# Power.net
KiCad netlist of a schematic drawn in Altium Designer
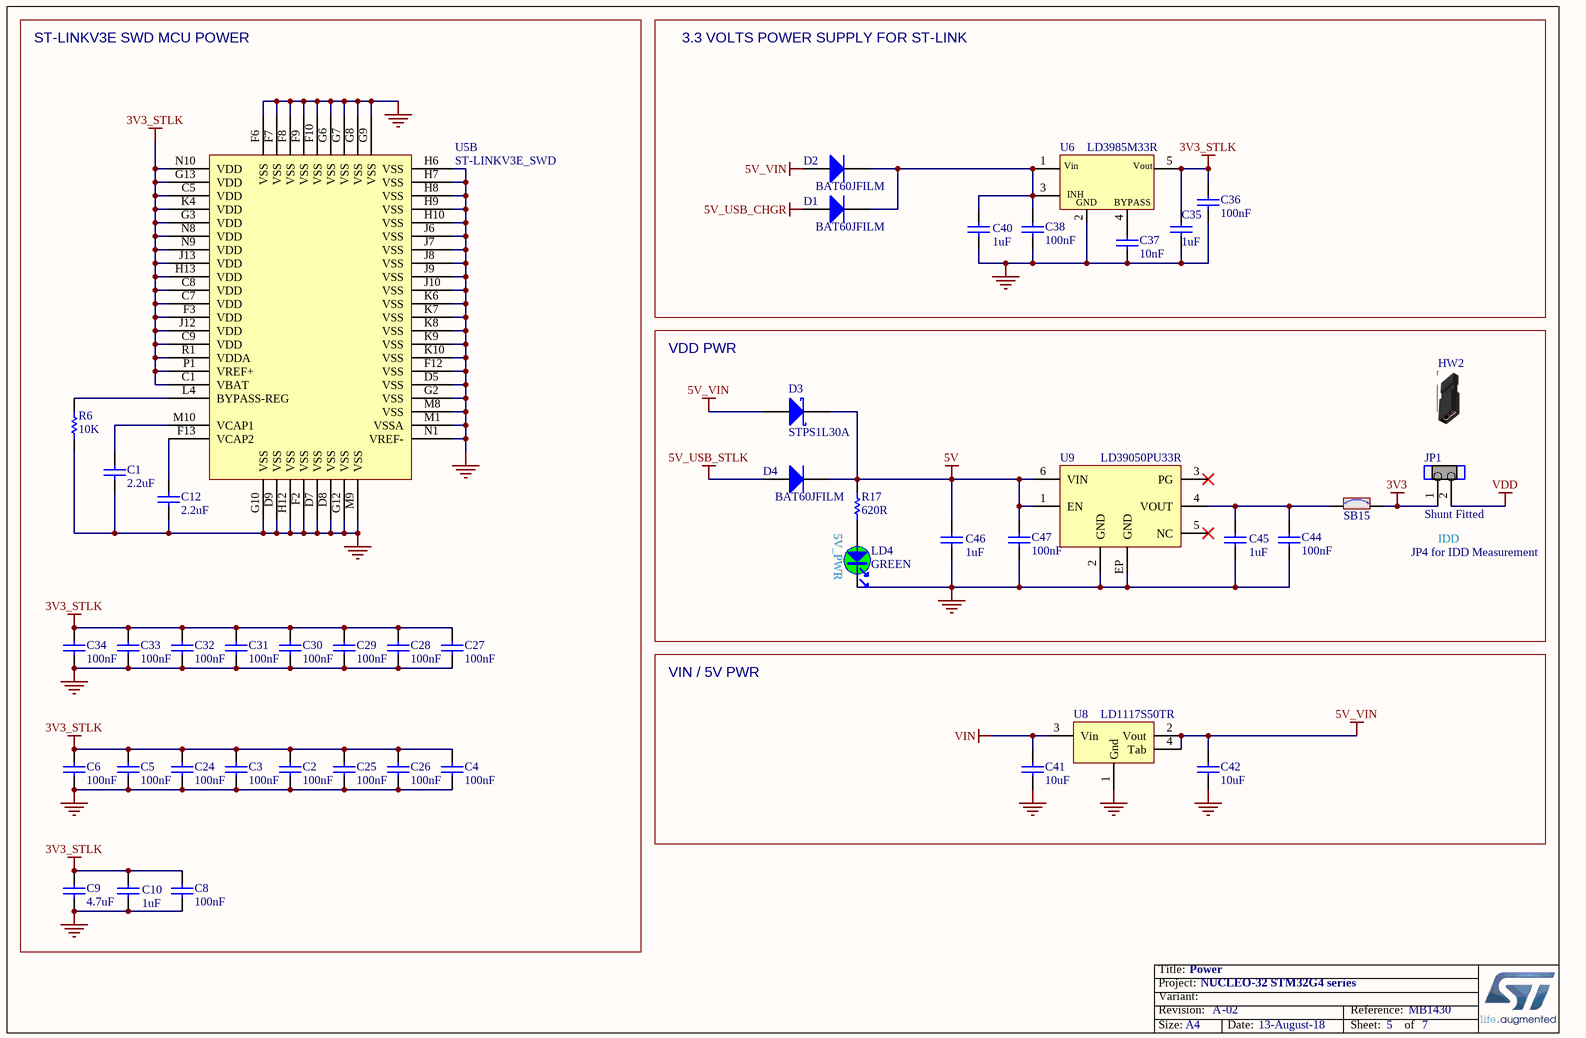
[diagram p0: Power.SchDoc]

(export (version "E")
  (design (tool "Eeschema 10.0.6"))
  (components
    (comp (ref "C1")
      (value "2.2uF")
      (footprint "C0603")
      (description "Capacitor, MLCC, 2.2uF, 10V, X5R, 10%, 0603, T=0,8mm")
      (fields
        (field (name "INTERNAL_PART_NUMBER") "MCD-00012")
        (field (name "MANUFACTURER_PART_NUMBER") "CC0603KRX5R6BB225")
        (field (name "PROVIDED_BY") "SUBCO")
      )
      (libsource (lib "MCD_PARTS_database") (part "Capacitor"))
    )
    (comp (ref "C2")
      (value "100nF")
      (footprint "C0402")
      (description "Capacitor, MLCC, 100nF, 16V, X7R, 10%, 0402, T=0,5mm")
      (fields
        (field (name "INTERNAL_PART_NUMBER") "MCD-00102")
        (field (name "MANUFACTURER_PART_NUMBER") "CC0402KRX7R7BB104")
        (field (name "PROVIDED_BY") "SUBCO")
      )
      (libsource (lib "MCD_PARTS_database") (part "Capacitor"))
    )
    (comp (ref "C3")
      (value "100nF")
      (footprint "C0402")
      (description "Capacitor, MLCC, 100nF, 16V, X7R, 10%, 0402, T=0,5mm")
      (fields
        (field (name "INTERNAL_PART_NUMBER") "MCD-00102")
        (field (name "MANUFACTURER_PART_NUMBER") "CC0402KRX7R7BB104")
        (field (name "PROVIDED_BY") "SUBCO")
      )
      (libsource (lib "MCD_PARTS_database") (part "Capacitor"))
    )
    (comp (ref "C4")
      (value "100nF")
      (footprint "C0402")
      (description "Capacitor, MLCC, 100nF, 16V, X7R, 10%, 0402, T=0,5mm")
      (fields
        (field (name "INTERNAL_PART_NUMBER") "MCD-00102")
        (field (name "MANUFACTURER_PART_NUMBER") "CC0402KRX7R7BB104")
        (field (name "PROVIDED_BY") "SUBCO")
      )
      (libsource (lib "MCD_PARTS_database") (part "Capacitor"))
    )
    (comp (ref "C5")
      (value "100nF")
      (footprint "C0402")
      (description "Capacitor, MLCC, 100nF, 16V, X7R, 10%, 0402, T=0,5mm")
      (fields
        (field (name "INTERNAL_PART_NUMBER") "MCD-00102")
        (field (name "MANUFACTURER_PART_NUMBER") "CC0402KRX7R7BB104")
        (field (name "PROVIDED_BY") "SUBCO")
      )
      (libsource (lib "MCD_PARTS_database") (part "Capacitor"))
    )
    (comp (ref "C6")
      (value "100nF")
      (footprint "C0402")
      (description "Capacitor, MLCC, 100nF, 16V, X7R, 10%, 0402, T=0,5mm")
      (fields
        (field (name "INTERNAL_PART_NUMBER") "MCD-00102")
        (field (name "MANUFACTURER_PART_NUMBER") "CC0402KRX7R7BB104")
        (field (name "PROVIDED_BY") "SUBCO")
      )
      (libsource (lib "MCD_PARTS_database") (part "Capacitor"))
    )
    (comp (ref "C8")
      (value "100nF")
      (footprint "C0402")
      (description "Capacitor, MLCC, 100nF, 16V, X7R, 10%, 0402, T=0,5mm")
      (fields
        (field (name "INTERNAL_PART_NUMBER") "MCD-00102")
        (field (name "MANUFACTURER_PART_NUMBER") "CC0402KRX7R7BB104")
        (field (name "PROVIDED_BY") "SUBCO")
      )
      (libsource (lib "MCD_PARTS_database") (part "Capacitor"))
    )
    (comp (ref "C9")
      (value "4.7uF")
      (footprint "C0603")
      (description "Capacitor, MLCC, 4.7uF, 16V, X5R, 10%, 0603, T=0.8mm")
      (fields
        (field (name "INTERNAL_PART_NUMBER") "MCD-00009")
        (field (name "MANUFACTURER_PART_NUMBER") "CC0603KRX5R7BB475")
        (field (name "PROVIDED_BY") "SUBCO")
      )
      (libsource (lib "MCD_PARTS_database") (part "Capacitor"))
    )
    (comp (ref "C10")
      (value "1uF")
      (footprint "C0603")
      (description "Capacitor, MLCC, 1uF, 16V, X5R, 10%, 0603, T=0,8mm")
      (fields
        (field (name "INTERNAL_PART_NUMBER") "MCD-00010")
        (field (name "MANUFACTURER_PART_NUMBER") "CC0603KRX5R7BB105")
        (field (name "PROVIDED_BY") "SUBCO")
      )
      (libsource (lib "MCD_PARTS_database") (part "Capacitor"))
    )
    (comp (ref "C12")
      (value "2.2uF")
      (footprint "C0603")
      (description "Capacitor, MLCC, 2.2uF, 10V, X5R, 10%, 0603, T=0,8mm")
      (fields
        (field (name "INTERNAL_PART_NUMBER") "MCD-00012")
        (field (name "MANUFACTURER_PART_NUMBER") "CC0603KRX5R6BB225")
        (field (name "PROVIDED_BY") "SUBCO")
      )
      (libsource (lib "MCD_PARTS_database") (part "Capacitor"))
    )
    (comp (ref "C24")
      (value "100nF")
      (footprint "C0402")
      (description "Capacitor, MLCC, 100nF, 16V, X7R, 10%, 0402, T=0,5mm")
      (fields
        (field (name "INTERNAL_PART_NUMBER") "MCD-00102")
        (field (name "MANUFACTURER_PART_NUMBER") "CC0402KRX7R7BB104")
        (field (name "PROVIDED_BY") "SUBCO")
      )
      (libsource (lib "MCD_PARTS_database") (part "Capacitor"))
    )
    (comp (ref "C25")
      (value "100nF")
      (footprint "C0402")
      (description "Capacitor, MLCC, 100nF, 16V, X7R, 10%, 0402, T=0,5mm")
      (fields
        (field (name "INTERNAL_PART_NUMBER") "MCD-00102")
        (field (name "MANUFACTURER_PART_NUMBER") "CC0402KRX7R7BB104")
        (field (name "PROVIDED_BY") "SUBCO")
      )
      (libsource (lib "MCD_PARTS_database") (part "Capacitor"))
    )
    (comp (ref "C26")
      (value "100nF")
      (footprint "C0402")
      (description "Capacitor, MLCC, 100nF, 16V, X7R, 10%, 0402, T=0,5mm")
      (fields
        (field (name "INTERNAL_PART_NUMBER") "MCD-00102")
        (field (name "MANUFACTURER_PART_NUMBER") "CC0402KRX7R7BB104")
        (field (name "PROVIDED_BY") "SUBCO")
      )
      (libsource (lib "MCD_PARTS_database") (part "Capacitor"))
    )
    (comp (ref "C27")
      (value "100nF")
      (footprint "C0402")
      (description "Capacitor, MLCC, 100nF, 16V, X7R, 10%, 0402, T=0,5mm")
      (fields
        (field (name "INTERNAL_PART_NUMBER") "MCD-00102")
        (field (name "MANUFACTURER_PART_NUMBER") "CC0402KRX7R7BB104")
        (field (name "PROVIDED_BY") "SUBCO")
      )
      (libsource (lib "MCD_PARTS_database") (part "Capacitor"))
    )
    (comp (ref "C28")
      (value "100nF")
      (footprint "C0402")
      (description "Capacitor, MLCC, 100nF, 16V, X7R, 10%, 0402, T=0,5mm")
      (fields
        (field (name "INTERNAL_PART_NUMBER") "MCD-00102")
        (field (name "MANUFACTURER_PART_NUMBER") "CC0402KRX7R7BB104")
        (field (name "PROVIDED_BY") "SUBCO")
      )
      (libsource (lib "MCD_PARTS_database") (part "Capacitor"))
    )
    (comp (ref "C29")
      (value "100nF")
      (footprint "C0402")
      (description "Capacitor, MLCC, 100nF, 16V, X7R, 10%, 0402, T=0,5mm")
      (fields
        (field (name "INTERNAL_PART_NUMBER") "MCD-00102")
        (field (name "MANUFACTURER_PART_NUMBER") "CC0402KRX7R7BB104")
        (field (name "PROVIDED_BY") "SUBCO")
      )
      (libsource (lib "MCD_PARTS_database") (part "Capacitor"))
    )
    (comp (ref "C30")
      (value "100nF")
      (footprint "C0402")
      (description "Capacitor, MLCC, 100nF, 16V, X7R, 10%, 0402, T=0,5mm")
      (fields
        (field (name "INTERNAL_PART_NUMBER") "MCD-00102")
        (field (name "MANUFACTURER_PART_NUMBER") "CC0402KRX7R7BB104")
        (field (name "PROVIDED_BY") "SUBCO")
      )
      (libsource (lib "MCD_PARTS_database") (part "Capacitor"))
    )
    (comp (ref "C31")
      (value "100nF")
      (footprint "C0402")
      (description "Capacitor, MLCC, 100nF, 16V, X7R, 10%, 0402, T=0,5mm")
      (fields
        (field (name "INTERNAL_PART_NUMBER") "MCD-00102")
        (field (name "MANUFACTURER_PART_NUMBER") "CC0402KRX7R7BB104")
        (field (name "PROVIDED_BY") "SUBCO")
      )
      (libsource (lib "MCD_PARTS_database") (part "Capacitor"))
    )
    (comp (ref "C32")
      (value "100nF")
      (footprint "C0402")
      (description "Capacitor, MLCC, 100nF, 16V, X7R, 10%, 0402, T=0,5mm")
      (fields
        (field (name "INTERNAL_PART_NUMBER") "MCD-00102")
        (field (name "MANUFACTURER_PART_NUMBER") "CC0402KRX7R7BB104")
        (field (name "PROVIDED_BY") "SUBCO")
      )
      (libsource (lib "MCD_PARTS_database") (part "Capacitor"))
    )
    (comp (ref "C33")
      (value "100nF")
      (footprint "C0402")
      (description "Capacitor, MLCC, 100nF, 16V, X7R, 10%, 0402, T=0,5mm")
      (fields
        (field (name "INTERNAL_PART_NUMBER") "MCD-00102")
        (field (name "MANUFACTURER_PART_NUMBER") "CC0402KRX7R7BB104")
        (field (name "PROVIDED_BY") "SUBCO")
      )
      (libsource (lib "MCD_PARTS_database") (part "Capacitor"))
    )
    (comp (ref "C34")
      (value "100nF")
      (footprint "C0402")
      (description "Capacitor, MLCC, 100nF, 16V, X7R, 10%, 0402, T=0,5mm")
      (fields
        (field (name "INTERNAL_PART_NUMBER") "MCD-00102")
        (field (name "MANUFACTURER_PART_NUMBER") "CC0402KRX7R7BB104")
        (field (name "PROVIDED_BY") "SUBCO")
      )
      (libsource (lib "MCD_PARTS_database") (part "Capacitor"))
    )
    (comp (ref "C35")
      (value "1uF")
      (footprint "C0603")
      (description "Capacitor, MLCC, 1uF, 16V, X5R, 10%, 0603, T=0,8mm")
      (fields
        (field (name "INTERNAL_PART_NUMBER") "MCD-00010")
        (field (name "MANUFACTURER_PART_NUMBER") "CC0603KRX5R7BB105")
        (field (name "PROVIDED_BY") "SUBCO")
      )
      (libsource (lib "MCD_PARTS_database") (part "Capacitor"))
    )
    (comp (ref "C36")
      (value "100nF")
      (footprint "C0402")
      (description "Capacitor, MLCC, 100nF, 16V, X7R, 10%, 0402, T=0,5mm")
      (fields
        (field (name "INTERNAL_PART_NUMBER") "MCD-00102")
        (field (name "MANUFACTURER_PART_NUMBER") "CC0402KRX7R7BB104")
        (field (name "PROVIDED_BY") "SUBCO")
      )
      (libsource (lib "MCD_PARTS_database") (part "Capacitor"))
    )
    (comp (ref "C37")
      (value "10nF")
      (footprint "C0402")
      (description "Capacitor, MLCC, 10nF, 16V, X7R, 10%, 0402, T=0.5mm")
      (fields
        (field (name "INTERNAL_PART_NUMBER") "MCD-00011")
        (field (name "MANUFACTURER_PART_NUMBER") "CC0402KRX7R7BB103")
        (field (name "PROVIDED_BY") "SUBCO")
      )
      (libsource (lib "MCD_PARTS_database") (part "Capacitor"))
    )
    (comp (ref "C38")
      (value "100nF")
      (footprint "C0402")
      (description "Capacitor, MLCC, 100nF, 16V, X7R, 10%, 0402, T=0,5mm")
      (fields
        (field (name "INTERNAL_PART_NUMBER") "MCD-00102")
        (field (name "MANUFACTURER_PART_NUMBER") "CC0402KRX7R7BB104")
        (field (name "PROVIDED_BY") "SUBCO")
      )
      (libsource (lib "MCD_PARTS_database") (part "Capacitor"))
    )
    (comp (ref "C40")
      (value "1uF")
      (footprint "C0603")
      (description "Capacitor, MLCC, 1uF, 16V, X5R, 10%, 0603, T=0,8mm")
      (fields
        (field (name "INTERNAL_PART_NUMBER") "MCD-00010")
        (field (name "MANUFACTURER_PART_NUMBER") "CC0603KRX5R7BB105")
        (field (name "PROVIDED_BY") "SUBCO")
      )
      (libsource (lib "MCD_PARTS_database") (part "Capacitor"))
    )
    (comp (ref "C41")
      (value "10uF")
      (footprint "C0805")
      (description "Capacitor, MLCC, 10uF, 25V, X5R, 10%, 0805, T=0,85mm")
      (fields
        (field (name "INTERNAL_PART_NUMBER") "MCD-00014")
        (field (name "MANUFACTURER_PART_NUMBER") "CC0805KRX5R8BB106")
        (field (name "PROVIDED_BY") "SUBCO")
      )
      (libsource (lib "MCD_PARTS_database") (part "Capacitor"))
    )
    (comp (ref "C42")
      (value "10uF")
      (footprint "C0805")
      (description "Capacitor, MLCC, 10uF, 25V, X5R, 10%, 0805, T=0,85mm")
      (fields
        (field (name "INTERNAL_PART_NUMBER") "MCD-00014")
        (field (name "MANUFACTURER_PART_NUMBER") "CC0805KRX5R8BB106")
        (field (name "PROVIDED_BY") "SUBCO")
      )
      (libsource (lib "MCD_PARTS_database") (part "Capacitor"))
    )
    (comp (ref "C44")
      (value "100nF")
      (footprint "C0402")
      (description "Capacitor, MLCC, 100nF, 16V, X7R, 10%, 0402, T=0,5mm")
      (fields
        (field (name "INTERNAL_PART_NUMBER") "MCD-00102")
        (field (name "MANUFACTURER_PART_NUMBER") "CC0402KRX7R7BB104")
        (field (name "PROVIDED_BY") "SUBCO")
      )
      (libsource (lib "MCD_PARTS_database") (part "Capacitor"))
    )
    (comp (ref "C45")
      (value "1uF")
      (footprint "C0603")
      (description "Capacitor, MLCC, 1uF, 16V, X5R, 10%, 0603, T=0,8mm")
      (fields
        (field (name "INTERNAL_PART_NUMBER") "MCD-00010")
        (field (name "MANUFACTURER_PART_NUMBER") "CC0603KRX5R7BB105")
        (field (name "PROVIDED_BY") "SUBCO")
      )
      (libsource (lib "MCD_PARTS_database") (part "Capacitor"))
    )
    (comp (ref "C46")
      (value "1uF")
      (footprint "C0603")
      (description "Capacitor, MLCC, 1uF, 16V, X5R, 10%, 0603, T=0,8mm")
      (fields
        (field (name "INTERNAL_PART_NUMBER") "MCD-00010")
        (field (name "MANUFACTURER_PART_NUMBER") "CC0603KRX5R7BB105")
        (field (name "PROVIDED_BY") "SUBCO")
      )
      (libsource (lib "MCD_PARTS_database") (part "Capacitor"))
    )
    (comp (ref "C47")
      (value "100nF")
      (footprint "C0402")
      (description "Capacitor, MLCC, 100nF, 16V, X7R, 10%, 0402, T=0,5mm")
      (fields
        (field (name "INTERNAL_PART_NUMBER") "MCD-00102")
        (field (name "MANUFACTURER_PART_NUMBER") "CC0402KRX7R7BB104")
        (field (name "PROVIDED_BY") "SUBCO")
      )
      (libsource (lib "MCD_PARTS_database") (part "Capacitor"))
    )
    (comp (ref "D1")
      (value "BAT60JFILM")
      (footprint "DIO_SOD323")
      (fields
        (field (name "INTERNAL_PART_NUMBER") "MCD-00034")
        (field (name "MANUFACTURER") "STMICROELECTRONICS")
        (field (name "BMS_PART_NUMBER") "9151097")
        (field (name "PROVIDED_BY") "SUBCO with ST control")
      )
      (libsource (lib "MCD_PARTS_database") (part "BAT60JFILM"))
    )
    (comp (ref "D2")
      (value "BAT60JFILM")
      (footprint "DIO_SOD323")
      (fields
        (field (name "INTERNAL_PART_NUMBER") "MCD-00034")
        (field (name "MANUFACTURER") "STMICROELECTRONICS")
        (field (name "BMS_PART_NUMBER") "9151097")
        (field (name "PROVIDED_BY") "SUBCO with ST control")
      )
      (libsource (lib "MCD_PARTS_database") (part "BAT60JFILM"))
    )
    (comp (ref "D3")
      (value "STPS1L30A")
      (footprint "DIO_SMA_1A_2K")
      (description "LOW DROP POWER SCHOTTKY RECTIFIER 1A 30V VF=0.3V")
      (fields
        (field (name "INTERNAL_PART_NUMBER") "MCD-01059")
        (field (name "MANUFACTURER") "STMICROELECTRONICS")
        (field (name "PROVIDED_BY") "SUBCO with ST control")
      )
      (libsource (lib "MCD_PARTS_database") (part "STPS1L40M"))
    )
    (comp (ref "D4")
      (value "BAT60JFILM")
      (footprint "DIO_SOD323")
      (fields
        (field (name "INTERNAL_PART_NUMBER") "MCD-00034")
        (field (name "MANUFACTURER") "STMICROELECTRONICS")
        (field (name "BMS_PART_NUMBER") "9151097")
        (field (name "PROVIDED_BY") "SUBCO with ST control")
      )
      (libsource (lib "MCD_PARTS_database") (part "BAT60JFILM"))
    )
    (comp (ref "HW2")
      (value "~")
      (description "SHUNT 1.27mm BLACK")
      (fields
        (field (name "INTERNAL_PART_NUMBER") "MCD-01409")
        (field (name "MANUFACTURER_PART_NUMBER") "266-101-10-00")
        (field (name "PROVIDED_BY") "SUBCO")
      )
      (libsource (lib "MCD_PARTS_database") (part "Shunt Black 1.27mm"))
    )
    (comp (ref "JP1")
      (value "Shunt Fitted")
      (footprint "CON_WP_707-2-02-2-20-00")
      (description "Header, 2x1, 1,27mm, Right Angled, Single Row, Height 3.05mm/1.27mm")
      (fields
        (field (name "INTERNAL_PART_NUMBER") "MCD-01428")
        (field (name "MANUFACTURER_PART_NUMBER") "707-2-02-2-20-00")
        (field (name "PROVIDED_BY") "SUBCO")
      )
      (libsource (lib "MCD_PARTS_database") (part "Jumper_Header1.27 2x1 Fitted"))
    )
    (comp (ref "LD4")
      (value "GREEN")
      (footprint "LED_0603_GREEN")
      (description "LED, Green, 0603")
      (fields
        (field (name "INTERNAL_PART_NUMBER") "MCD-00050")
        (field (name "MANUFACTURER_PART_NUMBER") "19-213SYGC/S530-E2/TR8")
        (field (name "PROVIDED_BY") "SUBCO")
      )
      (libsource (lib "MCD_PARTS_database") (part "LED_green"))
    )
    (comp (ref "R6")
      (value "10K")
      (footprint "R0402")
      (description "Resistor,10K,0402,1%,1/16W")
      (fields
        (field (name "INTERNAL_PART_NUMBER") "MCD-00053")
        (field (name "MANUFACTURER_PART_NUMBER") "RC0402FR-0710KL")
        (field (name "PROVIDED_BY") "SUBCO")
      )
      (libsource (lib "MCD_PARTS_database") (part "Resistor"))
    )
    (comp (ref "R17")
      (value "620R")
      (footprint "R0402")
      (description "Resistor,620R,0402,1%,1/16W")
      (fields
        (field (name "INTERNAL_PART_NUMBER") "MCD-00499")
        (field (name "MANUFACTURER_PART_NUMBER") "RC0402FR-07620RL")
        (field (name "PROVIDED_BY") "SUBCO")
      )
      (libsource (lib "MCD_PARTS_database") (part "Resistor"))
    )
    (comp (ref "SB15")
      (value "~")
      (footprint "SOLDER-BRIDGE_R0603-0R")
      (description "Solder Bridge ON")
      (fields
        (field (name "INTERNAL_PART_NUMBER") "MCD-00071")
        (field (name "MANUFACTURER_PART_NUMBER") "RC0603JR-070RL")
        (field (name "PROVIDED_BY") "SUBCO")
      )
      (libsource (lib "MCD_PARTS_database") (part "SB_ON"))
    )
    (comp (ref "U5")
      (value "ST-LINKV3E_SWD")
      (footprint "ICC_UFBGA201_176+25_10X10_P065")
      (description "STM32F723IEK  (STM32F7) BGA176")
      (fields
        (field (name "INTERNAL_PART_NUMBER") "MCD-00596")
        (field (name "MANUFACTURER_PART_NUMBER") "STM32F723IEK6")
        (field (name "PROVIDED_BY") "SUBCO with ST control")
      )
      (libsource (lib "MCD_PARTS_database") (part "ST-LINKV3E_SWD"))
    )
    (comp (ref "U6")
      (value "LD3985M33R")
      (footprint "REG_SOT23-5L")
      (description "Ultra low drop-low noise BiCMOS voltage, regulators low ESR capacitors compatible")
      (fields
        (field (name "INTERNAL_PART_NUMBER") "MCD-00086")
        (field (name "MANUFACTURER") "STMICROELECTRONICS")
        (field (name "PROVIDED_BY") "SUBCO with ST control")
      )
      (libsource (lib "MCD_PARTS_database") (part "LD3985M33R"))
    )
    (comp (ref "U8")
      (value "LD1117S50TR")
      (footprint "REG_SOT223-TAB")
      (description "IC REG LDO 5V 0.8A SOT223")
      (fields
        (field (name "INTERNAL_PART_NUMBER") "MCD-00088")
        (field (name "MANUFACTURER") "STMICROELECTRONICS")
        (field (name "PROVIDED_BY") "SUBCO with ST control")
      )
      (libsource (lib "MCD_PARTS_database") (part "LD1117S50TR"))
    )
    (comp (ref "U9")
      (value "LD39050PU33R")
      (footprint "ICC_DFN6-EPAD_3X3_P095")
      (description "Low quiescent current and low noise voltage regulators")
      (fields
        (field (name "INTERNAL_PART_NUMBER") "MCD-00215")
        (field (name "MANUFACTURER") "STMICROELECTRONICS")
        (field (name "PROVIDED_BY") "SUBCO with ST control")
      )
      (libsource (lib "MCD_PARTS_database") (part "LD39050PU33R"))
    )
  )
  (nets
    (net (code "1") (name "3V3") (class "Default")
      (node (ref "JP1") (pin "1") (pinfunction "1_1") (pintype "passive"))
      (node (ref "SB15") (pin "2") (pinfunction "2_2") (pintype "passive"))
    )
    (net (code "2") (name "3V3_STLK") (class "Default")
      (node (ref "C10") (pin "2") (pinfunction "2_2") (pintype "passive"))
      (node (ref "C2") (pin "2") (pinfunction "2_2") (pintype "passive"))
      (node (ref "C24") (pin "2") (pinfunction "2_2") (pintype "passive"))
      (node (ref "C25") (pin "2") (pinfunction "2_2") (pintype "passive"))
      (node (ref "C26") (pin "2") (pinfunction "2_2") (pintype "passive"))
      (node (ref "C27") (pin "2") (pinfunction "2_2") (pintype "passive"))
      (node (ref "C28") (pin "2") (pinfunction "2_2") (pintype "passive"))
      (node (ref "C29") (pin "2") (pinfunction "2_2") (pintype "passive"))
      (node (ref "C3") (pin "2") (pinfunction "2_2") (pintype "passive"))
      (node (ref "C30") (pin "2") (pinfunction "2_2") (pintype "passive"))
      (node (ref "C31") (pin "2") (pinfunction "2_2") (pintype "passive"))
      (node (ref "C32") (pin "2") (pinfunction "2_2") (pintype "passive"))
      (node (ref "C33") (pin "2") (pinfunction "2_2") (pintype "passive"))
      (node (ref "C34") (pin "2") (pinfunction "2_2") (pintype "passive"))
      (node (ref "C35") (pin "2") (pinfunction "2_2") (pintype "passive"))
      (node (ref "C36") (pin "2") (pinfunction "2_2") (pintype "passive"))
      (node (ref "C4") (pin "2") (pinfunction "2_2") (pintype "passive"))
      (node (ref "C5") (pin "2") (pinfunction "2_2") (pintype "passive"))
      (node (ref "C6") (pin "2") (pinfunction "2_2") (pintype "passive"))
      (node (ref "C8") (pin "2") (pinfunction "2_2") (pintype "passive"))
      (node (ref "C9") (pin "2") (pinfunction "2_2") (pintype "passive"))
      (node (ref "U5") (pin "C1") (pinfunction "VBAT_C1") (pintype "passive"))
      (node (ref "U5") (pin "C5") (pinfunction "VDD_C5") (pintype "passive"))
      (node (ref "U5") (pin "C7") (pinfunction "VDD_C7") (pintype "passive"))
      (node (ref "U5") (pin "C8") (pinfunction "VDD_C8") (pintype "passive"))
      (node (ref "U5") (pin "C9") (pinfunction "VDD_C9") (pintype "passive"))
      (node (ref "U5") (pin "F3") (pinfunction "VDD_F3") (pintype "passive"))
      (node (ref "U5") (pin "G13") (pinfunction "VDD_G13") (pintype "passive"))
      (node (ref "U5") (pin "G3") (pinfunction "VDD_G3") (pintype "passive"))
      (node (ref "U5") (pin "H13") (pinfunction "VDD_H13") (pintype "passive"))
      (node (ref "U5") (pin "J12") (pinfunction "VDD_J12") (pintype "passive"))
      (node (ref "U5") (pin "J13") (pinfunction "VDD_J13") (pintype "passive"))
      (node (ref "U5") (pin "K4") (pinfunction "VDD_K4") (pintype "passive"))
      (node (ref "U5") (pin "N10") (pinfunction "VDD_N10") (pintype "passive"))
      (node (ref "U5") (pin "N8") (pinfunction "VDD_N8") (pintype "passive"))
      (node (ref "U5") (pin "N9") (pinfunction "VDD_N9") (pintype "passive"))
      (node (ref "U5") (pin "P1") (pinfunction "VREF+_P1") (pintype "passive"))
      (node (ref "U5") (pin "R1") (pinfunction "VDDA_R1") (pintype "passive"))
      (node (ref "U6") (pin "5") (pinfunction "Vout_5") (pintype "passive"))
    )
    (net (code "3") (name "5V") (class "Default")
      (node (ref "C46") (pin "2") (pinfunction "2_2") (pintype "passive"))
      (node (ref "C47") (pin "2") (pinfunction "2_2") (pintype "passive"))
      (node (ref "D3") (pin "2") (pinfunction "K_2") (pintype "passive"))
      (node (ref "D4") (pin "2") (pinfunction "K_2") (pintype "passive"))
      (node (ref "R17") (pin "2") (pinfunction "2_2") (pintype "passive"))
      (node (ref "U9") (pin "1") (pinfunction "EN_1") (pintype "passive"))
      (node (ref "U9") (pin "6") (pinfunction "VIN_6") (pintype "passive"))
    )
    (net (code "4") (name "5V_USB_CHGR") (class "Default")
      (node (ref "D1") (pin "1") (pinfunction "A_1") (pintype "passive"))
    )
    (net (code "5") (name "5V_USB_STLK") (class "Default")
      (node (ref "D4") (pin "1") (pinfunction "A_1") (pintype "passive"))
    )
    (net (code "6") (name "5V_VIN") (class "Default")
      (node (ref "C42") (pin "2") (pinfunction "2_2") (pintype "passive"))
      (node (ref "D2") (pin "1") (pinfunction "A_1") (pintype "passive"))
      (node (ref "D3") (pin "1") (pinfunction "A_1") (pintype "passive"))
      (node (ref "U8") (pin "2") (pinfunction "Vout_2") (pintype "passive"))
      (node (ref "U8") (pin "4") (pinfunction "Tab_4") (pintype "passive"))
    )
    (net (code "7") (name "GND") (class "Default")
      (node (ref "C1") (pin "1") (pinfunction "1_1") (pintype "passive"))
      (node (ref "C10") (pin "1") (pinfunction "1_1") (pintype "passive"))
      (node (ref "C12") (pin "1") (pinfunction "1_1") (pintype "passive"))
      (node (ref "C2") (pin "1") (pinfunction "1_1") (pintype "passive"))
      (node (ref "C24") (pin "1") (pinfunction "1_1") (pintype "passive"))
      (node (ref "C25") (pin "1") (pinfunction "1_1") (pintype "passive"))
      (node (ref "C26") (pin "1") (pinfunction "1_1") (pintype "passive"))
      (node (ref "C27") (pin "1") (pinfunction "1_1") (pintype "passive"))
      (node (ref "C28") (pin "1") (pinfunction "1_1") (pintype "passive"))
      (node (ref "C29") (pin "1") (pinfunction "1_1") (pintype "passive"))
      (node (ref "C3") (pin "1") (pinfunction "1_1") (pintype "passive"))
      (node (ref "C30") (pin "1") (pinfunction "1_1") (pintype "passive"))
      (node (ref "C31") (pin "1") (pinfunction "1_1") (pintype "passive"))
      (node (ref "C32") (pin "1") (pinfunction "1_1") (pintype "passive"))
      (node (ref "C33") (pin "1") (pinfunction "1_1") (pintype "passive"))
      (node (ref "C34") (pin "1") (pinfunction "1_1") (pintype "passive"))
      (node (ref "C35") (pin "1") (pinfunction "1_1") (pintype "passive"))
      (node (ref "C36") (pin "1") (pinfunction "1_1") (pintype "passive"))
      (node (ref "C37") (pin "1") (pinfunction "1_1") (pintype "passive"))
      (node (ref "C38") (pin "1") (pinfunction "1_1") (pintype "passive"))
      (node (ref "C4") (pin "1") (pinfunction "1_1") (pintype "passive"))
      (node (ref "C40") (pin "1") (pinfunction "1_1") (pintype "passive"))
      (node (ref "C41") (pin "1") (pinfunction "1_1") (pintype "passive"))
      (node (ref "C42") (pin "1") (pinfunction "1_1") (pintype "passive"))
      (node (ref "C44") (pin "1") (pinfunction "1_1") (pintype "passive"))
      (node (ref "C45") (pin "1") (pinfunction "1_1") (pintype "passive"))
      (node (ref "C46") (pin "1") (pinfunction "1_1") (pintype "passive"))
      (node (ref "C47") (pin "1") (pinfunction "1_1") (pintype "passive"))
      (node (ref "C5") (pin "1") (pinfunction "1_1") (pintype "passive"))
      (node (ref "C6") (pin "1") (pinfunction "1_1") (pintype "passive"))
      (node (ref "C8") (pin "1") (pinfunction "1_1") (pintype "passive"))
      (node (ref "C9") (pin "1") (pinfunction "1_1") (pintype "passive"))
      (node (ref "LD4") (pin "2") (pintype "passive"))
      (node (ref "R6") (pin "1") (pinfunction "1_1") (pintype "passive"))
      (node (ref "U5") (pin "D5") (pinfunction "VSS_D5") (pintype "passive"))
      (node (ref "U5") (pin "D7") (pinfunction "VSS_D7") (pintype "passive"))
      (node (ref "U5") (pin "D8") (pinfunction "VSS_D8") (pintype "passive"))
      (node (ref "U5") (pin "D9") (pinfunction "VSS_D9") (pintype "passive"))
      (node (ref "U5") (pin "F10") (pinfunction "VSS_F10") (pintype "passive"))
      (node (ref "U5") (pin "F12") (pinfunction "VSS_F12") (pintype "passive"))
      (node (ref "U5") (pin "F2") (pinfunction "VSS_F2") (pintype "passive"))
      (node (ref "U5") (pin "F6") (pinfunction "VSS_F6") (pintype "passive"))
      (node (ref "U5") (pin "F7") (pinfunction "VSS_F7") (pintype "passive"))
      (node (ref "U5") (pin "F8") (pinfunction "VSS_F8") (pintype "passive"))
      (node (ref "U5") (pin "F9") (pinfunction "VSS_F9") (pintype "passive"))
      (node (ref "U5") (pin "G10") (pinfunction "VSS_G10") (pintype "passive"))
      (node (ref "U5") (pin "G12") (pinfunction "VSS_G12") (pintype "passive"))
      (node (ref "U5") (pin "G2") (pinfunction "VSS_G2") (pintype "passive"))
      (node (ref "U5") (pin "G6") (pinfunction "VSS_G6") (pintype "passive"))
      (node (ref "U5") (pin "G7") (pinfunction "VSS_G7") (pintype "passive"))
      (node (ref "U5") (pin "G8") (pinfunction "VSS_G8") (pintype "passive"))
      (node (ref "U5") (pin "G9") (pinfunction "VSS_G9") (pintype "passive"))
      (node (ref "U5") (pin "H10") (pinfunction "VSS_H10") (pintype "passive"))
      (node (ref "U5") (pin "H12") (pinfunction "VSS_H12") (pintype "passive"))
      (node (ref "U5") (pin "H6") (pinfunction "VSS_H6") (pintype "passive"))
      (node (ref "U5") (pin "H7") (pinfunction "VSS_H7") (pintype "passive"))
      (node (ref "U5") (pin "H8") (pinfunction "VSS_H8") (pintype "passive"))
      (node (ref "U5") (pin "H9") (pinfunction "VSS_H9") (pintype "passive"))
      (node (ref "U5") (pin "J10") (pinfunction "VSS_J10") (pintype "passive"))
      (node (ref "U5") (pin "J6") (pinfunction "VSS_J6") (pintype "passive"))
      (node (ref "U5") (pin "J7") (pinfunction "VSS_J7") (pintype "passive"))
      (node (ref "U5") (pin "J8") (pinfunction "VSS_J8") (pintype "passive"))
      (node (ref "U5") (pin "J9") (pinfunction "VSS_J9") (pintype "passive"))
      (node (ref "U5") (pin "K10") (pinfunction "VSS_K10") (pintype "passive"))
      (node (ref "U5") (pin "K6") (pinfunction "VSS_K6") (pintype "passive"))
      (node (ref "U5") (pin "K7") (pinfunction "VSS_K7") (pintype "passive"))
      (node (ref "U5") (pin "K8") (pinfunction "VSS_K8") (pintype "passive"))
      (node (ref "U5") (pin "K9") (pinfunction "VSS_K9") (pintype "passive"))
      (node (ref "U5") (pin "M1") (pinfunction "VSSA_M1") (pintype "passive"))
      (node (ref "U5") (pin "M8") (pinfunction "VSS_M8") (pintype "passive"))
      (node (ref "U5") (pin "M9") (pinfunction "VSS_M9") (pintype "passive"))
      (node (ref "U5") (pin "N1") (pinfunction "VREF-_N1") (pintype "passive"))
      (node (ref "U6") (pin "2") (pinfunction "GND_2") (pintype "passive"))
      (node (ref "U8") (pin "1") (pinfunction "Gnd_1") (pintype "passive"))
      (node (ref "U9") (pin "2") (pinfunction "GND_2") (pintype "passive"))
      (node (ref "U9") (pin "EP") (pinfunction "GND_EP") (pintype "passive"))
    )
    (net (code "8") (name "Net-(D1-K)") (class "Default")
      (node (ref "C38") (pin "2") (pinfunction "2_2") (pintype "passive"))
      (node (ref "C40") (pin "2") (pinfunction "2_2") (pintype "passive"))
      (node (ref "D1") (pin "2") (pinfunction "K_2") (pintype "passive"))
      (node (ref "D2") (pin "2") (pinfunction "K_2") (pintype "passive"))
      (node (ref "U6") (pin "1") (pinfunction "Vin_1") (pintype "passive"))
      (node (ref "U6") (pin "3") (pinfunction "CE_3") (pintype "passive"))
    )
    (net (code "9") (name "Net-(LD4-Pad1)") (class "Default")
      (node (ref "LD4") (pin "1") (pintype "passive"))
      (node (ref "R17") (pin "1") (pinfunction "1_1") (pintype "passive"))
    )
    (net (code "10") (name "Net-(U5B-BYPASS-REG)") (class "Default")
      (node (ref "R6") (pin "2") (pinfunction "2_2") (pintype "passive"))
      (node (ref "U5") (pin "L4") (pinfunction "BYPASS-REG_L4") (pintype "passive"))
    )
    (net (code "11") (name "Net-(U5B-VCAP1)") (class "Default")
      (node (ref "C1") (pin "2") (pinfunction "2_2") (pintype "passive"))
      (node (ref "U5") (pin "M10") (pinfunction "VCAP1_M10") (pintype "passive"))
    )
    (net (code "12") (name "Net-(U5B-VCAP2)") (class "Default")
      (node (ref "C12") (pin "2") (pinfunction "2_2") (pintype "passive"))
      (node (ref "U5") (pin "F13") (pinfunction "VCAP2_F13") (pintype "passive"))
    )
    (net (code "13") (name "Net-(U6-BYPASS)") (class "Default")
      (node (ref "C37") (pin "2") (pinfunction "2_2") (pintype "passive"))
      (node (ref "U6") (pin "4") (pinfunction "BYPASS_4") (pintype "passive"))
    )
    (net (code "14") (name "Net-(U9-VOUT)") (class "Default")
      (node (ref "C44") (pin "2") (pinfunction "2_2") (pintype "passive"))
      (node (ref "C45") (pin "2") (pinfunction "2_2") (pintype "passive"))
      (node (ref "SB15") (pin "1") (pinfunction "1_1") (pintype "passive"))
      (node (ref "U9") (pin "4") (pinfunction "VOUT_4") (pintype "passive"))
    )
    (net (code "15") (name "VDD") (class "Default")
      (node (ref "JP1") (pin "2") (pinfunction "2_2") (pintype "passive"))
    )
    (net (code "16") (name "VIN") (class "Default")
      (node (ref "C41") (pin "2") (pinfunction "2_2") (pintype "passive"))
      (node (ref "U8") (pin "3") (pinfunction "Vin_3") (pintype "passive"))
    )
    (net (code "17") (name "unconnected-(U9-NC-Pad5)") (class "Default")
      (node (ref "U9") (pin "5") (pinfunction "NC_5") (pintype "passive+no_connect"))
    )
    (net (code "18") (name "unconnected-(U9-PG-Pad3)") (class "Default")
      (node (ref "U9") (pin "3") (pinfunction "PG_3") (pintype "passive+no_connect"))
    )
  )
)
